# openSX70-dongle_v3-6.net
KiCad netlist of a schematic drawn in EAGLE
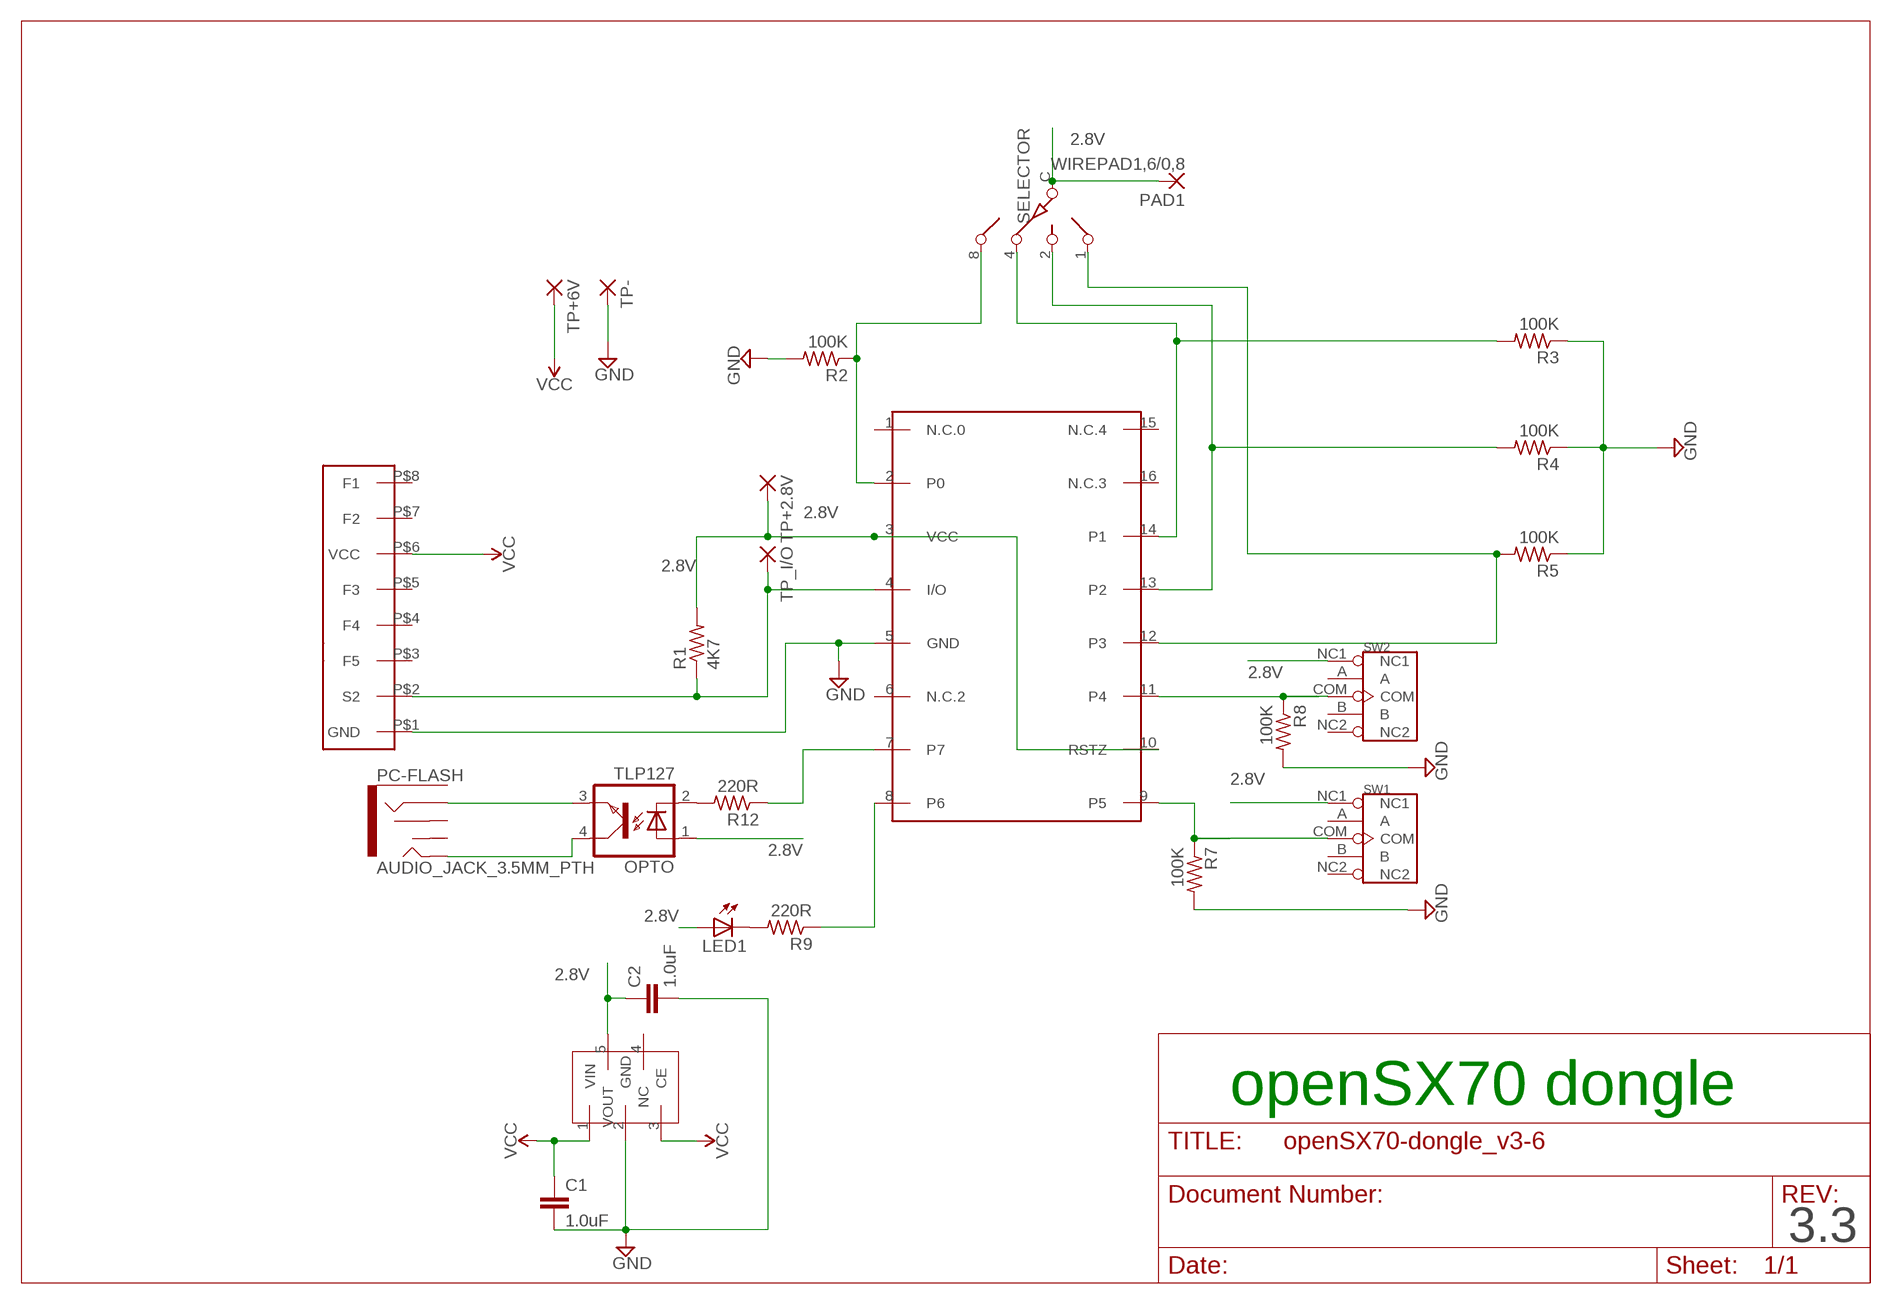
[diagram p0: schematic, sheet 1]

(export (version "E")
  (design (tool "Eeschema 10.0.6"))
  (components
    (comp (ref "C1")
      (value "1.0uF")
      (footprint "eagle-import:C0603")
      (libsource (lib "eagle-import") (part "C-EUC0603"))
    )
    (comp (ref "C2")
      (value "1.0uF")
      (footprint "eagle-import:C0603")
      (libsource (lib "eagle-import") (part "C-EUC0603"))
    )
    (comp (ref "DS2408")
      (value "DS2408")
      (footprint "eagle-import:SO16")
      (libsource (lib "eagle-import") (part "DS2408"))
    )
    (comp (ref "LED1")
      (value "LED3MM")
      (footprint "eagle-import:LED3MM")
      (libsource (lib "eagle-import") (part "LED3MM"))
    )
    (comp (ref "OPTO")
      (value "TLP127")
      (footprint "eagle-import:SO-4")
      (libsource (lib "eagle-import") (part "TLP127"))
    )
    (comp (ref "PAD1")
      (value "WIREPAD1,6/0,8")
      (footprint "eagle-import:1,6_0,8")
      (libsource (lib "eagle-import") (part "WIREPAD1,6/0,8"))
    )
    (comp (ref "PC-FLASH")
      (value "AUDIO_JACK_3.5MM_PTH")
      (footprint "eagle-import:AUDIO-JACK")
      (libsource (lib "eagle-import") (part "AUDIO_JACK_3.5MM_PTH"))
    )
    (comp (ref "R1")
      (value "4K7")
      (footprint "eagle-import:M0805")
      (libsource (lib "eagle-import") (part "R-US_M0805"))
    )
    (comp (ref "R2")
      (value "100K")
      (footprint "eagle-import:M0805")
      (libsource (lib "eagle-import") (part "R-US_M0805"))
    )
    (comp (ref "R3")
      (value "100K")
      (footprint "eagle-import:M0805")
      (libsource (lib "eagle-import") (part "R-US_M0805"))
    )
    (comp (ref "R4")
      (value "100K")
      (footprint "eagle-import:M0805")
      (libsource (lib "eagle-import") (part "R-US_M0805"))
    )
    (comp (ref "R5")
      (value "100K")
      (footprint "eagle-import:M0805")
      (libsource (lib "eagle-import") (part "R-US_M0805"))
    )
    (comp (ref "R7")
      (value "100K")
      (footprint "eagle-import:M0805")
      (libsource (lib "eagle-import") (part "R-US_M0805"))
    )
    (comp (ref "R8")
      (value "100K")
      (footprint "eagle-import:M0805")
      (libsource (lib "eagle-import") (part "R-US_M0805"))
    )
    (comp (ref "R9")
      (value "220R")
      (footprint "eagle-import:M0805")
      (libsource (lib "eagle-import") (part "R-US_M0805"))
    )
    (comp (ref "R12")
      (value "220R")
      (footprint "eagle-import:M0805")
      (libsource (lib "eagle-import") (part "R-US_M0805"))
    )
    (comp (ref "REG")
      (value "NCP4688")
      (footprint "eagle-import:SOT-23-5")
      (libsource (lib "eagle-import") (part "NCP4688"))
    )
    (comp (ref "SELECTOR")
      (value "SW-C16")
      (footprint "eagle-import:SW-C16")
      (libsource (lib "eagle-import") (part "SW-C16"))
    )
    (comp (ref "SW1")
      (value "DIP-TOGGLE-SWITCH-ON-ON(3+2P-8.8X4.6MM)-90D")
      (footprint "eagle-import:SW5-2.0-8.8X4.4X4.7MM-90D")
      (fields (field (name "MPN") "3P-2.0-90D3P-2.0-90D-REINFORCE"))
      (libsource (lib "eagle-import") (part "DIP-TOGGLE-SWITCH-ON-ON(3+2P-8.8X4.6MM)-90D"))
    )
    (comp (ref "SW2")
      (value "DIP-TOGGLE-SWITCH-ON-ON(3+2P-8.8X4.6MM)-90D")
      (footprint "eagle-import:SW5-2.0-8.8X4.4X4.7MM-90D")
      (fields (field (name "MPN") "3P-2.0-90D3P-2.0-90D-REINFORCE"))
      (libsource (lib "eagle-import") (part "DIP-TOGGLE-SWITCH-ON-ON(3+2P-8.8X4.6MM)-90D"))
    )
    (comp (ref "TP+2.8V")
      (value "SMD2")
      (footprint "eagle-import:SMD1,27-2,54")
      (libsource (lib "eagle-import") (part "SMD2"))
    )
    (comp (ref "TP+6V")
      (value "SMD2")
      (footprint "eagle-import:SMD1,27-2,54")
      (libsource (lib "eagle-import") (part "SMD2"))
    )
    (comp (ref "TP-")
      (value "SMD2")
      (footprint "eagle-import:SMD1,27-2,54")
      (libsource (lib "eagle-import") (part "SMD2"))
    )
    (comp (ref "TP_I/O")
      (value "SMD2")
      (footprint "eagle-import:SMD1,27-2,54")
      (libsource (lib "eagle-import") (part "SMD2"))
    )
    (comp (ref "U$1")
      (value "FLASH-EDGE-CONNECTOR")
      (footprint "eagle-import:FLASH-EDGE-8")
      (libsource (lib "eagle-import") (part "FLASH-EDGE-CONNECTOR"))
    )
  )
  (nets
    (net (code "1") (name "/2.8V") (class "Default")
      (node (ref "C2") (pin "1") (pinfunction "1_1") (pintype "passive"))
      (node (ref "DS2408") (pin "10") (pinfunction "RSTZ_10") (pintype "bidirectional"))
      (node (ref "DS2408") (pin "3") (pinfunction "VCC_3") (pintype "bidirectional"))
      (node (ref "LED1") (pin "A") (pinfunction "A_A") (pintype "passive"))
      (node (ref "OPTO") (pin "1") (pinfunction "A_1") (pintype "passive"))
      (node (ref "PAD1") (pin "1") (pinfunction "P_1") (pintype "passive"))
      (node (ref "R1") (pin "2") (pinfunction "2_2") (pintype "passive"))
      (node (ref "REG") (pin "5") (pinfunction "VOUT_5") (pintype "bidirectional"))
      (node (ref "SELECTOR") (pin "C") (pinfunction "C_C") (pintype "passive"))
      (node (ref "SW1") (pin "NC1") (pinfunction "NC1_NC1") (pintype "bidirectional"))
      (node (ref "SW2") (pin "NC1") (pinfunction "NC1_NC1") (pintype "bidirectional"))
      (node (ref "TP+2.8V") (pin "1") (pinfunction "P_1") (pintype "passive"))
    )
    (net (code "2") (name "GND") (class "Default")
      (node (ref "C1") (pin "2") (pinfunction "2_2") (pintype "passive"))
      (node (ref "C2") (pin "2") (pinfunction "2_2") (pintype "passive"))
      (node (ref "DS2408") (pin "5") (pinfunction "GND_5") (pintype "bidirectional"))
      (node (ref "R2") (pin "2") (pinfunction "2_2") (pintype "passive"))
      (node (ref "R3") (pin "1") (pinfunction "1_1") (pintype "passive"))
      (node (ref "R4") (pin "1") (pinfunction "1_1") (pintype "passive"))
      (node (ref "R5") (pin "1") (pinfunction "1_1") (pintype "passive"))
      (node (ref "R7") (pin "2") (pinfunction "2_2") (pintype "passive"))
      (node (ref "R8") (pin "2") (pinfunction "2_2") (pintype "passive"))
      (node (ref "REG") (pin "2") (pinfunction "GND_2") (pintype "bidirectional"))
      (node (ref "TP-") (pin "1") (pinfunction "P_1") (pintype "passive"))
      (node (ref "U$1") (pin "P$1") (pinfunction "GND_P$1") (pintype "bidirectional"))
    )
    (net (code "3") (name "Net-(DS2408-I{slash}O)") (class "Default")
      (node (ref "DS2408") (pin "4") (pinfunction "I/O_4") (pintype "bidirectional"))
      (node (ref "R1") (pin "1") (pinfunction "1_1") (pintype "passive"))
      (node (ref "TP_I/O") (pin "1") (pinfunction "P_1") (pintype "passive"))
      (node (ref "U$1") (pin "P$2") (pinfunction "S2_P$2") (pintype "bidirectional"))
    )
    (net (code "4") (name "Net-(DS2408-P0)") (class "Default")
      (node (ref "DS2408") (pin "2") (pinfunction "P0_2") (pintype "bidirectional"))
      (node (ref "R2") (pin "1") (pinfunction "1_1") (pintype "passive"))
      (node (ref "SELECTOR") (pin "8") (pinfunction "8_8") (pintype "passive"))
    )
    (net (code "5") (name "Net-(DS2408-P1)") (class "Default")
      (node (ref "DS2408") (pin "14") (pinfunction "P1_14") (pintype "bidirectional"))
      (node (ref "R3") (pin "2") (pinfunction "2_2") (pintype "passive"))
      (node (ref "SELECTOR") (pin "4") (pinfunction "4_4") (pintype "passive"))
    )
    (net (code "6") (name "Net-(DS2408-P2)") (class "Default")
      (node (ref "DS2408") (pin "13") (pinfunction "P2_13") (pintype "bidirectional"))
      (node (ref "R4") (pin "2") (pinfunction "2_2") (pintype "passive"))
      (node (ref "SELECTOR") (pin "2") (pinfunction "2_2") (pintype "passive"))
    )
    (net (code "7") (name "Net-(DS2408-P3)") (class "Default")
      (node (ref "DS2408") (pin "12") (pinfunction "P3_12") (pintype "bidirectional"))
      (node (ref "R5") (pin "2") (pinfunction "2_2") (pintype "passive"))
      (node (ref "SELECTOR") (pin "1") (pinfunction "1_1") (pintype "passive"))
    )
    (net (code "8") (name "Net-(DS2408-P4)") (class "Default")
      (node (ref "DS2408") (pin "11") (pinfunction "P4_11") (pintype "bidirectional"))
      (node (ref "R8") (pin "1") (pinfunction "1_1") (pintype "passive"))
      (node (ref "SW2") (pin "COM") (pinfunction "COM_COM") (pintype "bidirectional"))
    )
    (net (code "9") (name "Net-(DS2408-P5)") (class "Default")
      (node (ref "DS2408") (pin "9") (pinfunction "P5_9") (pintype "bidirectional"))
      (node (ref "R7") (pin "1") (pinfunction "1_1") (pintype "passive"))
      (node (ref "SW1") (pin "COM") (pinfunction "COM_COM") (pintype "bidirectional"))
    )
    (net (code "10") (name "Net-(DS2408-P6)") (class "Default")
      (node (ref "DS2408") (pin "8") (pinfunction "P6_8") (pintype "bidirectional"))
      (node (ref "R9") (pin "1") (pinfunction "1_1") (pintype "passive"))
    )
    (net (code "11") (name "Net-(DS2408-P7)") (class "Default")
      (node (ref "DS2408") (pin "7") (pinfunction "P7_7") (pintype "bidirectional"))
      (node (ref "R12") (pin "1") (pinfunction "1_1") (pintype "passive"))
    )
    (net (code "12") (name "Net-(LED1-C)") (class "Default")
      (node (ref "LED1") (pin "K") (pinfunction "C_K") (pintype "passive"))
      (node (ref "R9") (pin "2") (pinfunction "2_2") (pintype "passive"))
    )
    (net (code "13") (name "Net-(OPTO-C)") (class "Default")
      (node (ref "OPTO") (pin "2") (pinfunction "C_2") (pintype "passive"))
      (node (ref "R12") (pin "2") (pinfunction "2_2") (pintype "passive"))
    )
    (net (code "14") (name "Net-(OPTO-COL)") (class "Default")
      (node (ref "OPTO") (pin "4") (pinfunction "COL_4") (pintype "passive"))
      (node (ref "PC-FLASH") (pin "TIP") (pinfunction "TIP_TIP") (pintype "bidirectional"))
    )
    (net (code "15") (name "Net-(OPTO-EMIT)") (class "Default")
      (node (ref "OPTO") (pin "3") (pinfunction "EMIT_3") (pintype "passive"))
      (node (ref "PC-FLASH") (pin "RING") (pinfunction "RING_RING") (pintype "bidirectional"))
    )
    (net (code "16") (name "VCC") (class "Default")
      (node (ref "C1") (pin "1") (pinfunction "1_1") (pintype "passive"))
      (node (ref "REG") (pin "1") (pinfunction "VIN_1") (pintype "bidirectional"))
      (node (ref "REG") (pin "3") (pinfunction "CE_3") (pintype "bidirectional"))
      (node (ref "TP+6V") (pin "1") (pinfunction "P_1") (pintype "passive"))
      (node (ref "U$1") (pin "P$6") (pinfunction "VCC_P$6") (pintype "bidirectional"))
    )
    (net (code "17") (name "unconnected-(DS2408-N.C.0-Pad1)") (class "Default")
      (node (ref "DS2408") (pin "1") (pinfunction "N.C.0_1") (pintype "bidirectional"))
    )
    (net (code "18") (name "unconnected-(DS2408-N.C.2-Pad6)") (class "Default")
      (node (ref "DS2408") (pin "6") (pinfunction "N.C.2_6") (pintype "bidirectional"))
    )
    (net (code "19") (name "unconnected-(DS2408-N.C.3-Pad16)") (class "Default")
      (node (ref "DS2408") (pin "16") (pinfunction "N.C.3_16") (pintype "bidirectional"))
    )
    (net (code "20") (name "unconnected-(DS2408-N.C.4-Pad15)") (class "Default")
      (node (ref "DS2408") (pin "15") (pinfunction "N.C.4_15") (pintype "bidirectional"))
    )
    (net (code "21") (name "unconnected-(PC-FLASH-PadRSH)") (class "Default")
      (node (ref "PC-FLASH") (pin "RSH") (pinfunction "RSH_RSH") (pintype "bidirectional"))
    )
    (net (code "22") (name "unconnected-(PC-FLASH-PadSLEEVE)") (class "Default")
      (node (ref "PC-FLASH") (pin "SLEEVE") (pinfunction "SLEEVE_SLEEVE") (pintype "bidirectional"))
    )
    (net (code "23") (name "unconnected-(PC-FLASH-PadTSH)") (class "Default")
      (node (ref "PC-FLASH") (pin "TSH") (pinfunction "TSH_TSH") (pintype "bidirectional"))
    )
    (net (code "24") (name "unconnected-(REG-NC-Pad4)") (class "Default")
      (node (ref "REG") (pin "4") (pinfunction "NC_4") (pintype "bidirectional"))
    )
    (net (code "25") (name "unconnected-(SW1-PadA)") (class "Default")
      (node (ref "SW1") (pin "A") (pinfunction "A_A") (pintype "bidirectional"))
    )
    (net (code "26") (name "unconnected-(SW1-PadB)") (class "Default")
      (node (ref "SW1") (pin "B") (pinfunction "B_B") (pintype "bidirectional"))
    )
    (net (code "27") (name "unconnected-(SW1-PadNC2)") (class "Default")
      (node (ref "SW1") (pin "NC2") (pinfunction "NC2_NC2") (pintype "bidirectional"))
    )
    (net (code "28") (name "unconnected-(SW2-PadA)") (class "Default")
      (node (ref "SW2") (pin "A") (pinfunction "A_A") (pintype "bidirectional"))
    )
    (net (code "29") (name "unconnected-(SW2-PadB)") (class "Default")
      (node (ref "SW2") (pin "B") (pinfunction "B_B") (pintype "bidirectional"))
    )
    (net (code "30") (name "unconnected-(SW2-PadNC2)") (class "Default")
      (node (ref "SW2") (pin "NC2") (pinfunction "NC2_NC2") (pintype "bidirectional"))
    )
    (net (code "31") (name "unconnected-(U$1-F1-PadP$8)") (class "Default")
      (node (ref "U$1") (pin "P$8") (pinfunction "F1_P$8") (pintype "bidirectional"))
    )
    (net (code "32") (name "unconnected-(U$1-F2-PadP$7)") (class "Default")
      (node (ref "U$1") (pin "P$7") (pinfunction "F2_P$7") (pintype "bidirectional"))
    )
    (net (code "33") (name "unconnected-(U$1-F3-PadP$5)") (class "Default")
      (node (ref "U$1") (pin "P$5") (pinfunction "F3_P$5") (pintype "bidirectional"))
    )
    (net (code "34") (name "unconnected-(U$1-F4-PadP$4)") (class "Default")
      (node (ref "U$1") (pin "P$4") (pinfunction "F4_P$4") (pintype "bidirectional"))
    )
    (net (code "35") (name "unconnected-(U$1-F5-PadP$3)") (class "Default")
      (node (ref "U$1") (pin "P$3") (pinfunction "F5_P$3") (pintype "bidirectional"))
    )
  )
)
